# EMIRemover.net
KiCad netlist of a schematic drawn in Altium Designer
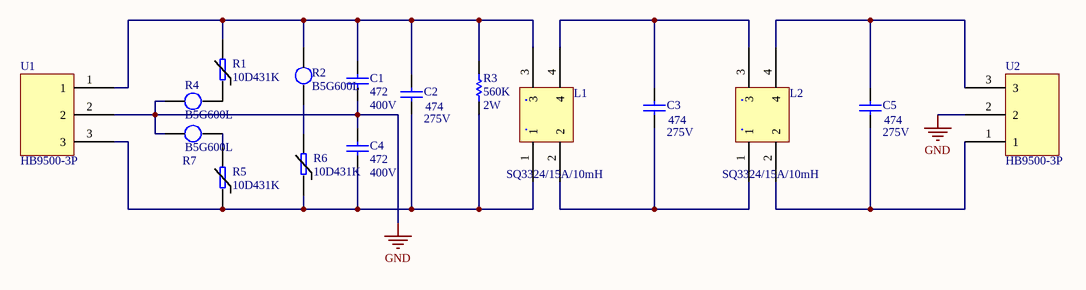
[diagram p0: EMIRemover.SchDoc]

(export (version "E")
  (design (tool "Eeschema 10.0.6"))
  (components
    (comp (ref "C1")
      (value "400V")
      (footprint "CNCPowerSupply:RAD-0.4")
      (description "Capacitor")
      (fields (field (name "ALTIUM_VALUE") "472") (field (name "PUBLISHER") "Altium Limited"))
      (libsource (lib "Miscellaneous Devices") (part "Cap"))
    )
    (comp (ref "C2")
      (value "275V")
      (footprint "CNCPowerSupply:CAPCDSPC")
      (description "Capacitor")
      (fields (field (name "ALTIUM_VALUE") "474") (field (name "PUBLISHER") "Altium Limited"))
      (libsource (lib "Miscellaneous Devices") (part "Cap"))
    )
    (comp (ref "C3")
      (value "275V")
      (footprint "CNCPowerSupply:CAPCDSPC")
      (description "Capacitor")
      (fields (field (name "ALTIUM_VALUE") "474") (field (name "PUBLISHER") "Altium Limited"))
      (libsource (lib "Miscellaneous Devices") (part "Cap"))
    )
    (comp (ref "C4")
      (value "400V")
      (footprint "CNCPowerSupply:RAD-0.4")
      (description "Capacitor")
      (fields (field (name "ALTIUM_VALUE") "472") (field (name "PUBLISHER") "Altium Limited"))
      (libsource (lib "Miscellaneous Devices") (part "Cap"))
    )
    (comp (ref "C5")
      (value "275V")
      (footprint "CNCPowerSupply:CAPCDSPC")
      (description "Capacitor")
      (fields (field (name "ALTIUM_VALUE") "474") (field (name "PUBLISHER") "Altium Limited"))
      (libsource (lib "Miscellaneous Devices") (part "Cap"))
    )
    (comp (ref "L1")
      (value "SQ3324/15A/10mH")
      (footprint "CNCPowerSupply:SQ3324")
      (description "SQ3324")
      (libsource (lib "CNCPowerSupply") (part "SQ3324"))
    )
    (comp (ref "L2")
      (value "SQ3324/15A/10mH")
      (footprint "CNCPowerSupply:SQ3324")
      (description "SQ3324")
      (libsource (lib "CNCPowerSupply") (part "SQ3324"))
    )
    (comp (ref "R1")
      (value "10D431K")
      (footprint "CNCPowerSupply:10D431K")
      (libsource (lib "CNCPowerSupply") (part "10D431K"))
    )
    (comp (ref "R2")
      (value "B5G600L")
      (footprint "CNCPowerSupply:B5G600L")
      (libsource (lib "CNCPowerSupply") (part "B5G600L"))
    )
    (comp (ref "R3")
      (value "2W")
      (footprint "CNCPowerSupply:AXIAL-0.7")
      (description "Resistor")
      (fields (field (name "ALTIUM_VALUE") "560K") (field (name "PUBLISHER") "Altium Limited"))
      (libsource (lib "Miscellaneous Devices") (part "Res1"))
    )
    (comp (ref "R4")
      (value "B5G600L")
      (footprint "CNCPowerSupply:B5G600L")
      (libsource (lib "CNCPowerSupply") (part "B5G600L"))
    )
    (comp (ref "R5")
      (value "10D431K")
      (footprint "CNCPowerSupply:10D431K")
      (libsource (lib "CNCPowerSupply") (part "10D431K"))
    )
    (comp (ref "R6")
      (value "10D431K")
      (footprint "CNCPowerSupply:10D431K")
      (libsource (lib "CNCPowerSupply") (part "10D431K"))
    )
    (comp (ref "R7")
      (value "B5G600L")
      (footprint "CNCPowerSupply:B5G600L")
      (libsource (lib "CNCPowerSupply") (part "B5G600L"))
    )
    (comp (ref "U1")
      (value "HB9500-3P")
      (footprint "CNCPowerSupply:HB9500-3P")
      (libsource (lib "") (part "HB9500-3P_1"))
    )
    (comp (ref "U2")
      (value "HB9500-3P")
      (footprint "CNCPowerSupply:HB9500-3P")
      (libsource (lib "CNCPowerSupply") (part "HB9500-3P"))
    )
  )
  (nets
    (net (code "1") (name "GND") (class "Default")
      (node (ref "C1") (pin "2") (pinfunction "2_2") (pintype "passive"))
      (node (ref "C4") (pin "1") (pinfunction "1_1") (pintype "passive"))
      (node (ref "R4") (pin "1") (pinfunction "1_1") (pintype "passive"))
      (node (ref "R7") (pin "1") (pinfunction "1_1") (pintype "passive"))
      (node (ref "U1") (pin "2") (pinfunction "2_2") (pintype "passive"))
      (node (ref "U2") (pin "2") (pinfunction "2_2") (pintype "passive"))
    )
    (net (code "2") (name "Net-(C1-Pad1)") (class "Default")
      (node (ref "C1") (pin "1") (pinfunction "1_1") (pintype "passive"))
      (node (ref "C2") (pin "1") (pinfunction "1_1") (pintype "passive"))
      (node (ref "L1") (pin "3") (pinfunction "3_3") (pintype "passive"))
      (node (ref "R1") (pin "1") (pinfunction "1_1") (pintype "passive"))
      (node (ref "R2") (pin "1") (pinfunction "1_1") (pintype "passive"))
      (node (ref "R3") (pin "1") (pinfunction "1_1") (pintype "passive"))
      (node (ref "U1") (pin "1") (pinfunction "1_1") (pintype "passive"))
    )
    (net (code "3") (name "Net-(C2-Pad2)") (class "Default")
      (node (ref "C2") (pin "2") (pinfunction "2_2") (pintype "passive"))
      (node (ref "C4") (pin "2") (pinfunction "2_2") (pintype "passive"))
      (node (ref "L1") (pin "1") (pinfunction "1_1") (pintype "passive"))
      (node (ref "R3") (pin "2") (pinfunction "2_2") (pintype "passive"))
      (node (ref "R5") (pin "2") (pinfunction "2_2") (pintype "passive"))
      (node (ref "R6") (pin "2") (pinfunction "2_2") (pintype "passive"))
      (node (ref "U1") (pin "3") (pinfunction "3_3") (pintype "passive"))
    )
    (net (code "4") (name "Net-(C3-Pad1)") (class "Default")
      (node (ref "C3") (pin "1") (pinfunction "1_1") (pintype "passive"))
      (node (ref "L1") (pin "4") (pinfunction "4_4") (pintype "passive"))
      (node (ref "L2") (pin "3") (pinfunction "3_3") (pintype "passive"))
    )
    (net (code "5") (name "Net-(C3-Pad2)") (class "Default")
      (node (ref "C3") (pin "2") (pinfunction "2_2") (pintype "passive"))
      (node (ref "L1") (pin "2") (pinfunction "2_2") (pintype "passive"))
      (node (ref "L2") (pin "1") (pinfunction "1_1") (pintype "passive"))
    )
    (net (code "6") (name "Net-(C5-Pad1)") (class "Default")
      (node (ref "C5") (pin "1") (pinfunction "1_1") (pintype "passive"))
      (node (ref "L2") (pin "4") (pinfunction "4_4") (pintype "passive"))
      (node (ref "U2") (pin "3") (pinfunction "3_3") (pintype "passive"))
    )
    (net (code "7") (name "Net-(C5-Pad2)") (class "Default")
      (node (ref "C5") (pin "2") (pinfunction "2_2") (pintype "passive"))
      (node (ref "L2") (pin "2") (pinfunction "2_2") (pintype "passive"))
      (node (ref "U2") (pin "1") (pinfunction "1_1") (pintype "passive"))
    )
    (net (code "8") (name "Net-(R1-Pad2)") (class "Default")
      (node (ref "R1") (pin "2") (pinfunction "2_2") (pintype "passive"))
      (node (ref "R4") (pin "2") (pinfunction "2_2") (pintype "passive"))
    )
    (net (code "9") (name "Net-(R2-Pad2)") (class "Default")
      (node (ref "R2") (pin "2") (pinfunction "2_2") (pintype "passive"))
      (node (ref "R6") (pin "1") (pinfunction "1_1") (pintype "passive"))
    )
    (net (code "10") (name "Net-(R5-Pad1)") (class "Default")
      (node (ref "R5") (pin "1") (pinfunction "1_1") (pintype "passive"))
      (node (ref "R7") (pin "2") (pinfunction "2_2") (pintype "passive"))
    )
  )
)
